# Power.net
KiCad netlist of a schematic drawn in Altium Designer
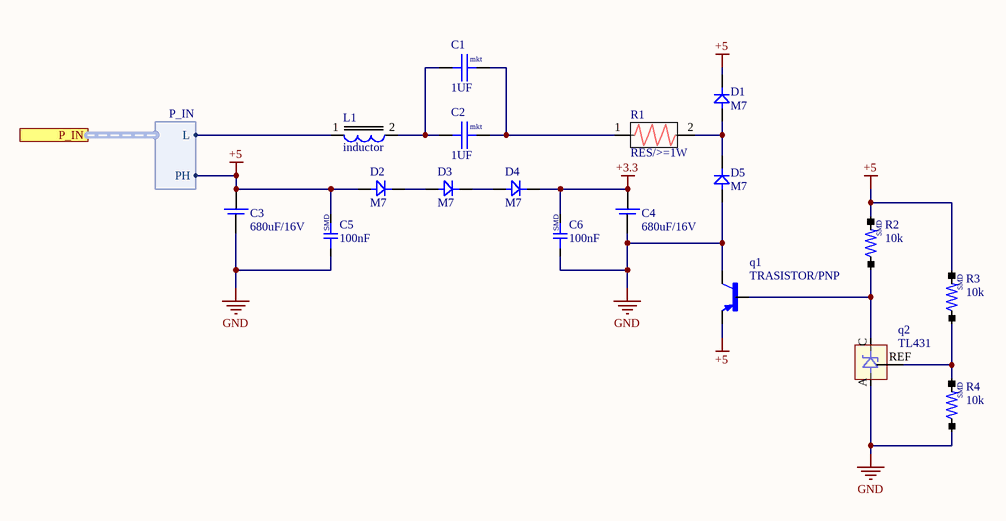
[diagram p0: Power.SchDoc]

(export (version "E")
  (design (tool "Eeschema 10.0.6"))
  (components
    (comp (ref "C1")
      (value "1UF")
      (footprint "CAP/0.22uF/275v/mkt")
      (libsource (lib "kave-eng-pro") (part "cap-mkt"))
    )
    (comp (ref "C2")
      (value "1UF")
      (footprint "CAP/0.22uF/275v/mkt")
      (libsource (lib "kave-eng-pro") (part "cap-mkt"))
    )
    (comp (ref "C3")
      (value "680uF/16V")
      (footprint "cap/330u/16v")
      (libsource (lib "kave-eng-pro") (part "cap-electrolit"))
    )
    (comp (ref "C4")
      (value "680uF/16V")
      (footprint "cap/330u/16v")
      (libsource (lib "kave-eng-pro") (part "cap-electrolit"))
    )
    (comp (ref "C5") (value "100nF") (footprint "CAP-0805") (libsource (lib "kave-eng-pro") (part "cap_smd")))
    (comp (ref "C6") (value "100nF") (footprint "CAP-0805") (libsource (lib "kave-eng-pro") (part "cap_smd")))
    (comp (ref "D1")
      (value "M7")
      (footprint "DIOD/1N4007/SMD")
      (libsource (lib "kave-eng-pro") (part "DIOD/RECTIFIERS"))
    )
    (comp (ref "D2")
      (value "M7")
      (footprint "DIOD/1N4007/SMD")
      (libsource (lib "kave-eng-pro") (part "DIOD/RECTIFIERS"))
    )
    (comp (ref "D3")
      (value "M7")
      (footprint "DIOD/1N4007/SMD")
      (libsource (lib "kave-eng-pro") (part "DIOD/RECTIFIERS"))
    )
    (comp (ref "D4")
      (value "M7")
      (footprint "DIOD/1N4007/SMD")
      (libsource (lib "kave-eng-pro") (part "DIOD/RECTIFIERS"))
    )
    (comp (ref "D5")
      (value "M7")
      (footprint "DIOD/1N4007/SMD")
      (libsource (lib "kave-eng-pro") (part "DIOD/RECTIFIERS"))
    )
    (comp (ref "L1")
      (value "inductor")
      (footprint "inductor-9*12")
      (libsource (lib "kave-eng-pro") (part "inductor"))
    )
    (comp (ref "q1")
      (value "TRASISTOR/PNP")
      (footprint "BC557")
      (libsource (lib "kave-eng-pro") (part "TRASISTOR/PNP"))
    )
    (comp (ref "q2") (value "TL431") (footprint "TL431") (libsource (lib "kave-eng-pro") (part "TL431")))
    (comp (ref "R1")
      (value "RES/>=1W")
      (footprint "RES/1W")
      (libsource (lib "kave-eng-pro") (part "RES/{gt}=1W"))
    )
    (comp (ref "R2") (value "10k") (footprint "RES/0805") (libsource (lib "kave-eng-pro") (part "RES/SMD")))
    (comp (ref "R3") (value "10k") (footprint "RES/0805") (libsource (lib "kave-eng-pro") (part "RES/SMD")))
    (comp (ref "R4") (value "10k") (footprint "RES/0805") (libsource (lib "kave-eng-pro") (part "RES/SMD")))
  )
  (nets
    (net (code "2") (name "+3.3") (class "Default")
      (node (ref "C4") (pin "+") (pintype "passive"))
      (node (ref "C6") (pin "2") (pintype "passive"))
      (node (ref "D4") (pin "K") (pintype "passive"))
    )
    (net (code "3") (name "+5") (class "Default")
      (node (ref "C3") (pin "+") (pintype "passive"))
      (node (ref "C5") (pin "2") (pintype "passive"))
      (node (ref "D1") (pin "K") (pintype "passive"))
      (node (ref "D2") (pin "A") (pintype "passive"))
      (node (ref "R2") (pin "2") (pinfunction "2_2") (pintype "passive"))
      (node (ref "R3") (pin "2") (pinfunction "2_2") (pintype "passive"))
      (node (ref "q1") (pin "E") (pinfunction "E_E") (pintype "passive"))
    )
    (net (code "4") (name "/L") (class "Default") (node (ref "L1") (pin "1") (pintype "passive")))
    (net (code "6") (name "GND") (class "Default")
      (node (ref "C3") (pin "-") (pintype "passive"))
      (node (ref "C4") (pin "-") (pintype "passive"))
      (node (ref "C5") (pin "1") (pintype "passive"))
      (node (ref "C6") (pin "1") (pintype "passive"))
      (node (ref "D5") (pin "A") (pintype "passive"))
      (node (ref "R4") (pin "1") (pinfunction "1_1") (pintype "passive"))
      (node (ref "q1") (pin "C") (pinfunction "C_C") (pintype "passive"))
      (node (ref "q2") (pin "A") (pintype "passive"))
    )
    (net (code "7") (name "Net-(C1-Pad1)") (class "Default")
      (node (ref "C1") (pin "1") (pintype "passive"))
      (node (ref "C2") (pin "1") (pintype "passive"))
      (node (ref "L1") (pin "2") (pintype "passive"))
    )
    (net (code "8") (name "Net-(C1-Pad2)") (class "Default")
      (node (ref "C1") (pin "2") (pintype "passive"))
      (node (ref "C2") (pin "2") (pintype "passive"))
      (node (ref "R1") (pin "1") (pintype "passive"))
    )
    (net (code "9") (name "Net-(D1-PadA)") (class "Default")
      (node (ref "D1") (pin "A") (pintype "passive"))
      (node (ref "D5") (pin "K") (pintype "passive"))
      (node (ref "R1") (pin "2") (pintype "passive"))
    )
    (net (code "10") (name "Net-(D2-PadK)") (class "Default")
      (node (ref "D2") (pin "K") (pintype "passive"))
      (node (ref "D3") (pin "A") (pintype "passive"))
    )
    (net (code "11") (name "Net-(D3-PadK)") (class "Default")
      (node (ref "D3") (pin "K") (pintype "passive"))
      (node (ref "D4") (pin "A") (pintype "passive"))
    )
    (net (code "12") (name "Net-(R2-Pad1)") (class "Default")
      (node (ref "R2") (pin "1") (pinfunction "1_1") (pintype "passive"))
      (node (ref "q1") (pin "B") (pinfunction "B_B") (pintype "passive"))
      (node (ref "q2") (pin "C") (pintype "passive"))
    )
    (net (code "13") (name "Net-(R3-Pad1)") (class "Default")
      (node (ref "R3") (pin "1") (pinfunction "1_1") (pintype "passive"))
      (node (ref "R4") (pin "2") (pinfunction "2_2") (pintype "passive"))
      (node (ref "q2") (pin "REF") (pintype "passive"))
    )
  )
)
